# pj7.net
KiCad netlist of a schematic drawn in EAGLE
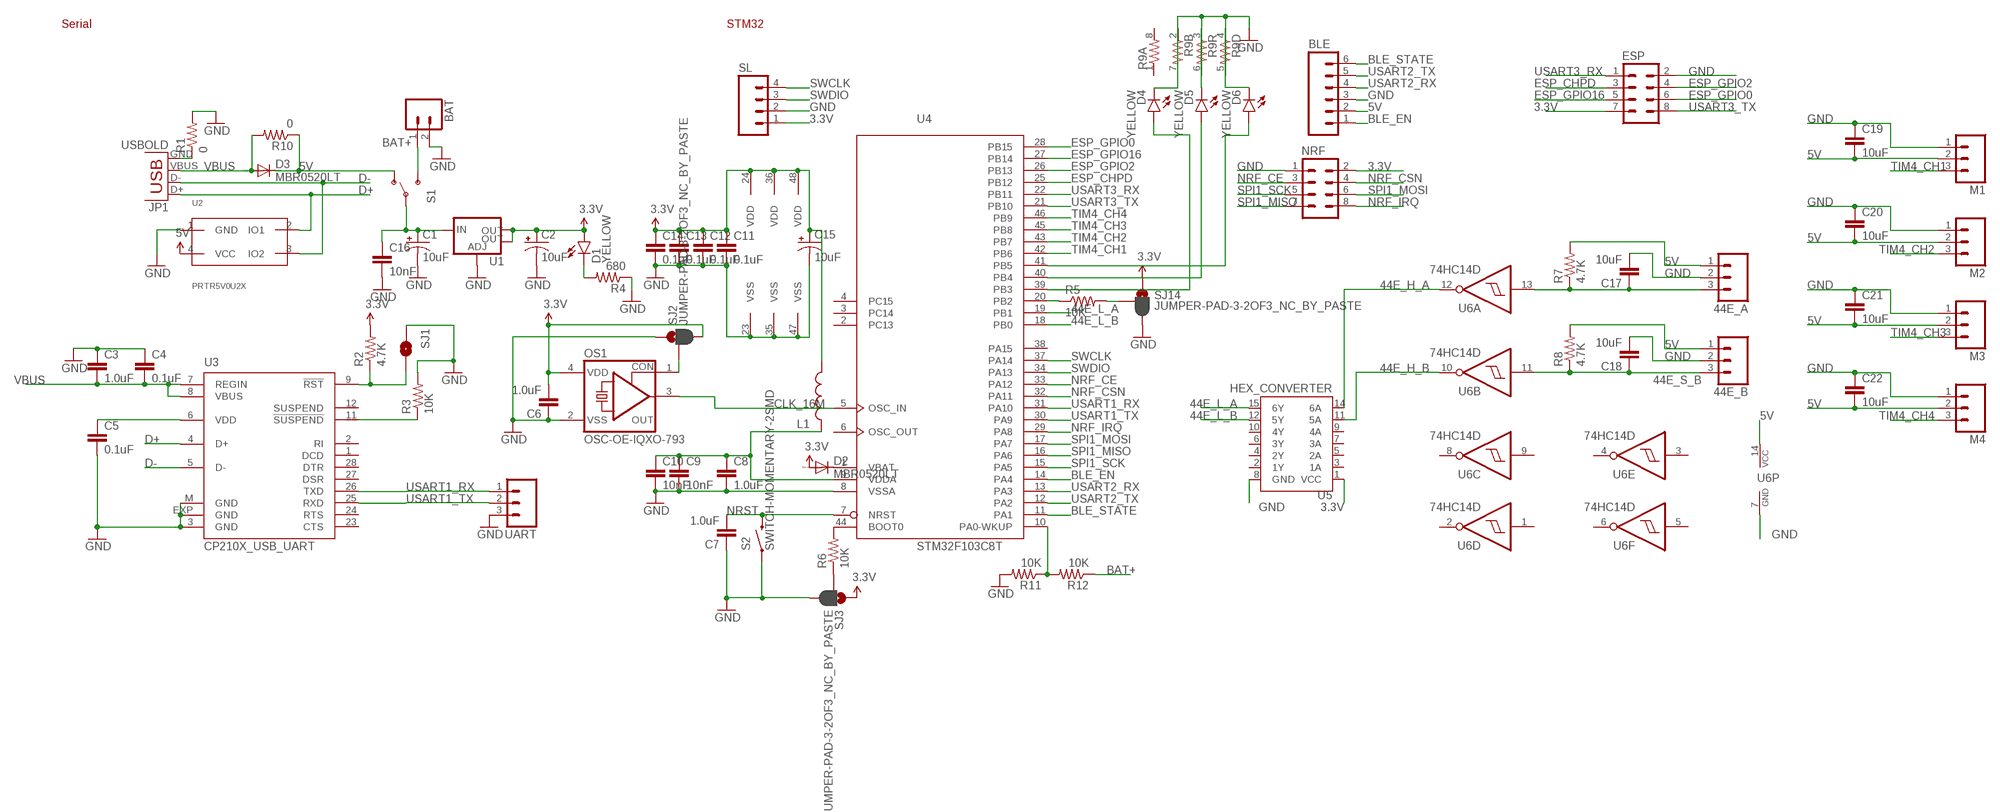
[diagram p0: schematic, sheet 1]

(export (version "E")
  (design (tool "Eeschema 10.0.6"))
  (components
    (comp (ref "44E_A")
      (value "M03LOCK")
      (footprint "eagle-import:1X03_LOCK")
      (libsource (lib "eagle-import") (part "M03LOCK"))
    )
    (comp (ref "44E_B")
      (value "M03LOCK")
      (footprint "eagle-import:1X03_LOCK")
      (libsource (lib "eagle-import") (part "M03LOCK"))
    )
    (comp (ref "BAT")
      (value "M02LOCK")
      (footprint "eagle-import:1X02_LOCK")
      (libsource (lib "eagle-import") (part "M02LOCK"))
    )
    (comp (ref "BLE")
      (value "M06LOCK")
      (footprint "eagle-import:1X06_LOCK")
      (libsource (lib "eagle-import") (part "M06LOCK"))
    )
    (comp (ref "C1")
      (value "10uF")
      (footprint "eagle-import:EIA3216")
      (libsource (lib "eagle-import") (part "10UF-16V-10%(TANT)"))
    )
    (comp (ref "C2")
      (value "10uF")
      (footprint "eagle-import:EIA3216")
      (libsource (lib "eagle-import") (part "10UF-16V-10%(TANT)"))
    )
    (comp (ref "C3")
      (value "1.0uF")
      (footprint "eagle-import:0603-CAP")
      (libsource (lib "eagle-import") (part "1.0UF-16V-10%(0603)"))
    )
    (comp (ref "C4")
      (value "0.1uF")
      (footprint "eagle-import:0603-CAP")
      (libsource (lib "eagle-import") (part "0.1UF-25V-5%(0603)"))
    )
    (comp (ref "C5")
      (value "0.1uF")
      (footprint "eagle-import:0603-CAP")
      (libsource (lib "eagle-import") (part "0.1UF-25V-5%(0603)"))
    )
    (comp (ref "C6")
      (value "1.0uF")
      (footprint "eagle-import:0603-CAP")
      (libsource (lib "eagle-import") (part "1.0UF-16V-10%(0603)"))
    )
    (comp (ref "C7")
      (value "1.0uF")
      (footprint "eagle-import:0603-CAP")
      (libsource (lib "eagle-import") (part "1.0UF-16V-10%(0603)"))
    )
    (comp (ref "C8")
      (value "1.0uF")
      (footprint "eagle-import:0603-CAP")
      (libsource (lib "eagle-import") (part "1.0UF-16V-10%(0603)"))
    )
    (comp (ref "C9")
      (value "10nF")
      (footprint "eagle-import:0603-CAP")
      (libsource (lib "eagle-import") (part "10NF/10000PF-50V-10%(0603)"))
    )
    (comp (ref "C10")
      (value "10nF")
      (footprint "eagle-import:0603-CAP")
      (libsource (lib "eagle-import") (part "10NF/10000PF-50V-10%(0603)"))
    )
    (comp (ref "C11")
      (value "0.1uF")
      (footprint "eagle-import:0603-CAP")
      (libsource (lib "eagle-import") (part "0.1UF-25V-5%(0603)"))
    )
    (comp (ref "C12")
      (value "0.1uF")
      (footprint "eagle-import:0603-CAP")
      (libsource (lib "eagle-import") (part "0.1UF-25V-5%(0603)"))
    )
    (comp (ref "C13")
      (value "0.1uF")
      (footprint "eagle-import:0603-CAP")
      (libsource (lib "eagle-import") (part "0.1UF-25V-5%(0603)"))
    )
    (comp (ref "C14")
      (value "0.1uF")
      (footprint "eagle-import:0603-CAP")
      (libsource (lib "eagle-import") (part "0.1UF-25V-5%(0603)"))
    )
    (comp (ref "C15")
      (value "10uF")
      (footprint "eagle-import:EIA3216")
      (libsource (lib "eagle-import") (part "10UF-16V-10%(TANT)"))
    )
    (comp (ref "C16")
      (value "10nF")
      (footprint "eagle-import:0603-CAP")
      (libsource (lib "eagle-import") (part "10NF/10000PF-50V-10%(0603)"))
    )
    (comp (ref "C17")
      (value "10uF")
      (footprint "eagle-import:0603-CAP")
      (libsource (lib "eagle-import") (part "10UF-6.3V-20%(0603)"))
    )
    (comp (ref "C18")
      (value "10uF")
      (footprint "eagle-import:0603-CAP")
      (libsource (lib "eagle-import") (part "10UF-6.3V-20%(0603)"))
    )
    (comp (ref "C19")
      (value "10uF")
      (footprint "eagle-import:0603-CAP")
      (libsource (lib "eagle-import") (part "10UF-6.3V-20%(0603)"))
    )
    (comp (ref "C20")
      (value "10uF")
      (footprint "eagle-import:0603-CAP")
      (libsource (lib "eagle-import") (part "10UF-6.3V-20%(0603)"))
    )
    (comp (ref "C21")
      (value "10uF")
      (footprint "eagle-import:0603-CAP")
      (libsource (lib "eagle-import") (part "10UF-6.3V-20%(0603)"))
    )
    (comp (ref "C22")
      (value "10uF")
      (footprint "eagle-import:0603-CAP")
      (libsource (lib "eagle-import") (part "10UF-6.3V-20%(0603)"))
    )
    (comp (ref "D1")
      (value "YELLOW")
      (footprint "eagle-import:LED-1206")
      (libsource (lib "eagle-import") (part "LED-YELLOW1206"))
    )
    (comp (ref "D2")
      (value "MBR0520LT")
      (footprint "eagle-import:SOD123")
      (libsource (lib "eagle-import") (part "MBR0520LT"))
    )
    (comp (ref "D3")
      (value "MBR0520LT")
      (footprint "eagle-import:SOD123")
      (libsource (lib "eagle-import") (part "MBR0520LT"))
    )
    (comp (ref "D4")
      (value "YELLOW")
      (footprint "eagle-import:LED-1206")
      (libsource (lib "eagle-import") (part "LED-YELLOW1206"))
    )
    (comp (ref "D5")
      (value "YELLOW")
      (footprint "eagle-import:LED-1206")
      (libsource (lib "eagle-import") (part "LED-YELLOW1206"))
    )
    (comp (ref "D6")
      (value "YELLOW")
      (footprint "eagle-import:LED-1206")
      (libsource (lib "eagle-import") (part "LED-YELLOW1206"))
    )
    (comp (ref "ESP")
      (value "M04X2DIP")
      (footprint "eagle-import:2X4")
      (libsource (lib "eagle-import") (part "M04X2DIP"))
    )
    (comp (ref "JP1")
      (value "USBOLD")
      (footprint "eagle-import:USB-MINIB-OLD")
      (libsource (lib "eagle-import") (part "USBOLD"))
    )
    (comp (ref "L1")
      (value "INDUCTOR0603")
      (footprint "eagle-import:0603")
      (libsource (lib "eagle-import") (part "INDUCTOR0603"))
    )
    (comp (ref "M1")
      (value "M03LOCK")
      (footprint "eagle-import:1X03_LOCK")
      (libsource (lib "eagle-import") (part "M03LOCK"))
    )
    (comp (ref "M2")
      (value "M03LOCK")
      (footprint "eagle-import:1X03_LOCK")
      (libsource (lib "eagle-import") (part "M03LOCK"))
    )
    (comp (ref "M3")
      (value "M03LOCK")
      (footprint "eagle-import:1X03_LOCK")
      (libsource (lib "eagle-import") (part "M03LOCK"))
    )
    (comp (ref "M4")
      (value "M03LOCK")
      (footprint "eagle-import:1X03_LOCK")
      (libsource (lib "eagle-import") (part "M03LOCK"))
    )
    (comp (ref "NRF")
      (value "M04X2DIP")
      (footprint "eagle-import:2X4")
      (libsource (lib "eagle-import") (part "M04X2DIP"))
    )
    (comp (ref "OS1")
      (value "OSC-OE-IQXO-793")
      (footprint "eagle-import:2.5X2-4-PAD")
      (libsource (lib "eagle-import") (part "OSC-OE-IQXO-793"))
    )
    (comp (ref "R1")
      (value "0")
      (footprint "eagle-import:0603")
      (libsource (lib "eagle-import") (part "0OHM-1/10W-5%(0603)"))
    )
    (comp (ref "R2")
      (value "4.7K")
      (footprint "eagle-import:0603-RES")
      (libsource (lib "eagle-import") (part "4.7KOHM-1/10W-1%(0603)"))
    )
    (comp (ref "R3")
      (value "10K")
      (footprint "eagle-import:0603-RES")
      (libsource (lib "eagle-import") (part "4.7KOHM-1/10W-1%(0603)"))
    )
    (comp (ref "R4")
      (value "680")
      (footprint "eagle-import:0603-RES")
      (libsource (lib "eagle-import") (part "680OHM1/10W5%(0603)"))
    )
    (comp (ref "R5")
      (value "10K")
      (footprint "eagle-import:0603-RES")
      (libsource (lib "eagle-import") (part "10KOHM-1/10W-1%(0603)0603"))
    )
    (comp (ref "R6")
      (value "10K")
      (footprint "eagle-import:0603-RES")
      (libsource (lib "eagle-import") (part "10KOHM-1/10W-1%(0603)0603"))
    )
    (comp (ref "R7")
      (value "4.7K")
      (footprint "eagle-import:0603-RES")
      (libsource (lib "eagle-import") (part "4.7KOHM-1/10W-1%(0603)"))
    )
    (comp (ref "R8")
      (value "4.7K")
      (footprint "eagle-import:0603-RES")
      (libsource (lib "eagle-import") (part "4.7KOHM-1/10W-1%(0603)"))
    )
    (comp (ref "R9")
      (value "RESISTOR-ARRAY0603-ARV")
      (footprint "eagle-import:0603-ARV")
      (libsource (lib "eagle-import") (part "RESISTOR-ARRAY0603-ARV"))
    )
    (comp (ref "R10")
      (value "0")
      (footprint "eagle-import:0603")
      (libsource (lib "eagle-import") (part "0OHM-1/10W-5%(0603)"))
    )
    (comp (ref "R11")
      (value "10K")
      (footprint "eagle-import:0603-RES")
      (libsource (lib "eagle-import") (part "10KOHM-1/10W-1%(0603)0603"))
    )
    (comp (ref "R12")
      (value "10K")
      (footprint "eagle-import:0603-RES")
      (libsource (lib "eagle-import") (part "10KOHM-1/10W-1%(0603)0603"))
    )
    (comp (ref "S1")
      (value "SWITCH-SPDTSMD")
      (footprint "eagle-import:AYZ0202")
      (libsource (lib "eagle-import") (part "SWITCH-SPDTSMD"))
    )
    (comp (ref "S2")
      (value "SWITCH-MOMENTARY-2SMD")
      (footprint "eagle-import:TACTILE-SWITCH-SMD")
      (libsource (lib "eagle-import") (part "SWITCH-MOMENTARY-2SMD"))
    )
    (comp (ref "SJ1")
      (value "JUMPER-PAD-2-NOYES_SILK")
      (footprint "eagle-import:PAD-JUMPER-2-NO_YES_SILK")
      (libsource (lib "eagle-import") (part "JUMPER-PAD-2-NOYES_SILK"))
    )
    (comp (ref "SJ2")
      (value "JUMPER-PAD-3-2OF3_NC_BY_PASTE")
      (footprint "eagle-import:PAD-JUMPER-3-2OF3_NC_BY_PASTE_YES_SILK_FULL_BOX")
      (libsource (lib "eagle-import") (part "JUMPER-PAD-3-2OF3_NC_BY_PASTE"))
    )
    (comp (ref "SJ3")
      (value "JUMPER-PAD-3-2OF3_NC_BY_PASTE")
      (footprint "eagle-import:PAD-JUMPER-3-2OF3_NC_BY_PASTE_YES_SILK_FULL_BOX")
      (libsource (lib "eagle-import") (part "JUMPER-PAD-3-2OF3_NC_BY_PASTE"))
    )
    (comp (ref "SJ14")
      (value "JUMPER-PAD-3-2OF3_NC_BY_PASTE")
      (footprint "eagle-import:PAD-JUMPER-3-2OF3_NC_BY_PASTE_YES_SILK_FULL_BOX")
      (libsource (lib "eagle-import") (part "JUMPER-PAD-3-2OF3_NC_BY_PASTE"))
    )
    (comp (ref "SL")
      (value "M04LOCK")
      (footprint "eagle-import:1X04_LOCK")
      (libsource (lib "eagle-import") (part "M04LOCK"))
    )
    (comp (ref "U1")
      (value "V_REG_LM1117SOT223")
      (footprint "eagle-import:SOT223")
      (libsource (lib "eagle-import") (part "V_REG_LM1117SOT223"))
    )
    (comp (ref "U2")
      (value "PRTR5V0U2X")
      (footprint "eagle-import:SOT143")
      (libsource (lib "eagle-import") (part "PRTR5V0U2X"))
    )
    (comp (ref "U3")
      (value "CP210X_USB_UART")
      (footprint "eagle-import:MLP28")
      (libsource (lib "eagle-import") (part "CP210X_USB_UART"))
    )
    (comp (ref "U4")
      (value "STM32F103C8T")
      (footprint "eagle-import:LQFP48")
      (libsource (lib "eagle-import") (part "STM32F103CT8"))
    )
    (comp (ref "U5")
      (value "HEX_CONVERTER")
      (footprint "eagle-import:SO016")
      (libsource (lib "eagle-import") (part "HEX_CONVERTER"))
    )
    (comp (ref "U6")
      (value "74HC14D")
      (footprint "eagle-import:SO14")
      (libsource (lib "eagle-import") (part "7414DHC"))
    )
    (comp (ref "UART")
      (value "M03LOCK")
      (footprint "eagle-import:1X03_LOCK")
      (libsource (lib "eagle-import") (part "M03LOCK"))
    )
  )
  (nets
    (net (code "1") (name "/44E_H_A") (class "Default")
      (node (ref "U5") (pin "14") (pinfunction "6A_14") (pintype "bidirectional"))
      (node (ref "U6") (pin "12") (pinfunction "O_12") (pintype "output"))
    )
    (net (code "2") (name "/44E_H_B") (class "Default")
      (node (ref "U5") (pin "11") (pinfunction "5A_11") (pintype "bidirectional"))
      (node (ref "U6") (pin "10") (pinfunction "O_10") (pintype "output"))
    )
    (net (code "3") (name "/44E_L_A") (class "Default")
      (node (ref "U4") (pin "19") (pinfunction "PB1_19") (pintype "bidirectional"))
      (node (ref "U5") (pin "15") (pinfunction "6Y_15") (pintype "bidirectional"))
    )
    (net (code "4") (name "/44E_L_B") (class "Default")
      (node (ref "U4") (pin "18") (pinfunction "PB0_18") (pintype "bidirectional"))
      (node (ref "U5") (pin "12") (pinfunction "5Y_12") (pintype "bidirectional"))
    )
    (net (code "5") (name "/44E_S_B") (class "Default")
      (node (ref "44E_B") (pin "3") (pinfunction "3_3") (pintype "passive"))
      (node (ref "C18") (pin "1") (pinfunction "1_1") (pintype "passive"))
      (node (ref "R8") (pin "1") (pinfunction "1_1") (pintype "passive"))
      (node (ref "U6") (pin "11") (pinfunction "I_11") (pintype "input"))
    )
    (net (code "6") (name "/BAT+") (class "Default")
      (node (ref "BAT") (pin "1") (pinfunction "1_1") (pintype "passive"))
      (node (ref "R12") (pin "1") (pinfunction "1_1") (pintype "passive"))
      (node (ref "S1") (pin "3") (pinfunction "S_3") (pintype "passive"))
    )
    (net (code "7") (name "/BLE_EN") (class "Default")
      (node (ref "BLE") (pin "1") (pinfunction "1_1") (pintype "passive"))
      (node (ref "U4") (pin "14") (pinfunction "PA4_14") (pintype "bidirectional"))
    )
    (net (code "8") (name "/BLE_STATE") (class "Default")
      (node (ref "BLE") (pin "6") (pinfunction "6_6") (pintype "passive"))
      (node (ref "U4") (pin "11") (pinfunction "PA1_11") (pintype "bidirectional"))
    )
    (net (code "9") (name "/CLK_16M") (class "Default")
      (node (ref "OS1") (pin "3") (pinfunction "OUT_3") (pintype "output"))
      (node (ref "U4") (pin "5") (pinfunction "OSC_IN_5") (pintype "bidirectional"))
    )
    (net (code "10") (name "/D+") (class "Default")
      (node (ref "JP1") (pin "D+") (pinfunction "D+_D+") (pintype "bidirectional"))
      (node (ref "U2") (pin "2") (pinfunction "IO1_2") (pintype "bidirectional"))
      (node (ref "U3") (pin "4") (pinfunction "D+_4") (pintype "bidirectional"))
    )
    (net (code "11") (name "/D-") (class "Default")
      (node (ref "JP1") (pin "D-") (pinfunction "D-_D-") (pintype "bidirectional"))
      (node (ref "U2") (pin "3") (pinfunction "IO2_3") (pintype "bidirectional"))
      (node (ref "U3") (pin "5") (pinfunction "D-_5") (pintype "bidirectional"))
    )
    (net (code "12") (name "/ESP_CHPD") (class "Default")
      (node (ref "ESP") (pin "3") (pinfunction "3_3") (pintype "passive"))
      (node (ref "U4") (pin "25") (pinfunction "PB12_25") (pintype "bidirectional"))
    )
    (net (code "13") (name "/ESP_GPIO0") (class "Default")
      (node (ref "ESP") (pin "6") (pinfunction "6_6") (pintype "passive"))
      (node (ref "U4") (pin "28") (pinfunction "PB15_28") (pintype "bidirectional"))
    )
    (net (code "14") (name "/ESP_GPIO2") (class "Default")
      (node (ref "ESP") (pin "4") (pinfunction "4_4") (pintype "passive"))
      (node (ref "U4") (pin "26") (pinfunction "PB13_26") (pintype "bidirectional"))
    )
    (net (code "15") (name "/ESP_GPIO16") (class "Default")
      (node (ref "ESP") (pin "5") (pinfunction "5_5") (pintype "passive"))
      (node (ref "U4") (pin "27") (pinfunction "PB14_27") (pintype "bidirectional"))
    )
    (net (code "16") (name "/NRF_CE") (class "Default")
      (node (ref "NRF") (pin "3") (pinfunction "3_3") (pintype "passive"))
      (node (ref "U4") (pin "33") (pinfunction "PA12_33") (pintype "bidirectional"))
    )
    (net (code "17") (name "/NRF_CSN") (class "Default")
      (node (ref "NRF") (pin "4") (pinfunction "4_4") (pintype "passive"))
      (node (ref "U4") (pin "32") (pinfunction "PA11_32") (pintype "bidirectional"))
    )
    (net (code "18") (name "/NRF_IRQ") (class "Default")
      (node (ref "NRF") (pin "8") (pinfunction "8_8") (pintype "passive"))
      (node (ref "U4") (pin "29") (pinfunction "PA8_29") (pintype "bidirectional"))
    )
    (net (code "19") (name "/NRST") (class "Default")
      (node (ref "C7") (pin "2") (pinfunction "2_2") (pintype "passive"))
      (node (ref "S2") (pin "3") (pinfunction "2_3") (pintype "passive"))
      (node (ref "U4") (pin "7") (pinfunction "NRST_7") (pintype "bidirectional"))
    )
    (net (code "20") (name "/SPI1_MISO") (class "Default")
      (node (ref "NRF") (pin "7") (pinfunction "7_7") (pintype "passive"))
      (node (ref "U4") (pin "16") (pinfunction "PA6_16") (pintype "bidirectional"))
    )
    (net (code "21") (name "/SPI1_MOSI") (class "Default")
      (node (ref "NRF") (pin "6") (pinfunction "6_6") (pintype "passive"))
      (node (ref "U4") (pin "17") (pinfunction "PA7_17") (pintype "bidirectional"))
    )
    (net (code "22") (name "/SPI1_SCK") (class "Default")
      (node (ref "NRF") (pin "5") (pinfunction "5_5") (pintype "passive"))
      (node (ref "U4") (pin "15") (pinfunction "PA5_15") (pintype "bidirectional"))
    )
    (net (code "23") (name "/SWCLK") (class "Default")
      (node (ref "SL") (pin "4") (pinfunction "4_4") (pintype "passive"))
      (node (ref "U4") (pin "37") (pinfunction "PA14_37") (pintype "bidirectional"))
    )
    (net (code "24") (name "/SWDIO") (class "Default")
      (node (ref "SL") (pin "3") (pinfunction "3_3") (pintype "passive"))
      (node (ref "U4") (pin "34") (pinfunction "PA13_34") (pintype "bidirectional"))
    )
    (net (code "25") (name "/TIM4_CH1") (class "Default")
      (node (ref "M1") (pin "3") (pinfunction "3_3") (pintype "passive"))
      (node (ref "U4") (pin "42") (pinfunction "PB6_42") (pintype "bidirectional"))
    )
    (net (code "26") (name "/TIM4_CH2") (class "Default")
      (node (ref "M2") (pin "3") (pinfunction "3_3") (pintype "passive"))
      (node (ref "U4") (pin "43") (pinfunction "PB7_43") (pintype "bidirectional"))
    )
    (net (code "27") (name "/TIM4_CH3") (class "Default")
      (node (ref "M3") (pin "3") (pinfunction "3_3") (pintype "passive"))
      (node (ref "U4") (pin "45") (pinfunction "PB8_45") (pintype "bidirectional"))
    )
    (net (code "28") (name "/TIM4_CH4") (class "Default")
      (node (ref "M4") (pin "3") (pinfunction "3_3") (pintype "passive"))
      (node (ref "U4") (pin "46") (pinfunction "PB9_46") (pintype "bidirectional"))
    )
    (net (code "29") (name "/USART1_RX") (class "Default")
      (node (ref "U3") (pin "26") (pinfunction "TXD_26") (pintype "output"))
      (node (ref "U4") (pin "31") (pinfunction "PA10_31") (pintype "bidirectional"))
      (node (ref "UART") (pin "1") (pinfunction "1_1") (pintype "passive"))
    )
    (net (code "30") (name "/USART1_TX") (class "Default")
      (node (ref "U3") (pin "25") (pinfunction "RXD_25") (pintype "input"))
      (node (ref "U4") (pin "30") (pinfunction "PA9_30") (pintype "bidirectional"))
      (node (ref "UART") (pin "2") (pinfunction "2_2") (pintype "passive"))
    )
    (net (code "31") (name "/USART2_RX") (class "Default")
      (node (ref "BLE") (pin "4") (pinfunction "4_4") (pintype "passive"))
      (node (ref "U4") (pin "13") (pinfunction "PA3_13") (pintype "bidirectional"))
    )
    (net (code "32") (name "/USART2_TX") (class "Default")
      (node (ref "BLE") (pin "5") (pinfunction "5_5") (pintype "passive"))
      (node (ref "U4") (pin "12") (pinfunction "PA2_12") (pintype "bidirectional"))
    )
    (net (code "33") (name "/USART3_RX") (class "Default")
      (node (ref "ESP") (pin "1") (pinfunction "1_1") (pintype "passive"))
      (node (ref "U4") (pin "22") (pinfunction "PB11_22") (pintype "bidirectional"))
    )
    (net (code "34") (name "/USART3_TX") (class "Default")
      (node (ref "ESP") (pin "8") (pinfunction "8_8") (pintype "passive"))
      (node (ref "U4") (pin "21") (pinfunction "PB10_21") (pintype "bidirectional"))
    )
    (net (code "35") (name "/VBUS") (class "Default")
      (node (ref "C3") (pin "2") (pinfunction "2_2") (pintype "passive"))
      (node (ref "C4") (pin "2") (pinfunction "2_2") (pintype "passive"))
      (node (ref "D3") (pin "A") (pinfunction "A_A") (pintype "passive"))
      (node (ref "JP1") (pin "VBUS") (pinfunction "VBUS_VBUS") (pintype "bidirectional"))
      (node (ref "R10") (pin "2") (pinfunction "2_2") (pintype "passive"))
      (node (ref "U3") (pin "7") (pinfunction "REGIN_7") (pintype "passive"))
      (node (ref "U3") (pin "8") (pinfunction "VBUS_8") (pintype "input"))
    )
    (net (code "36") (name "3.3V") (class "Default")
      (node (ref "C11") (pin "1") (pinfunction "1_1") (pintype "passive"))
      (node (ref "C12") (pin "1") (pinfunction "1_1") (pintype "passive"))
      (node (ref "C13") (pin "1") (pinfunction "1_1") (pintype "passive"))
      (node (ref "C14") (pin "1") (pinfunction "1_1") (pintype "passive"))
      (node (ref "C15") (pin "A") (pinfunction "+_A") (pintype "passive"))
      (node (ref "C2") (pin "A") (pinfunction "+_A") (pintype "passive"))
      (node (ref "C6") (pin "2") (pinfunction "2_2") (pintype "passive"))
      (node (ref "D1") (pin "A") (pinfunction "A_A") (pintype "passive"))
      (node (ref "D2") (pin "A") (pinfunction "A_A") (pintype "passive"))
      (node (ref "ESP") (pin "7") (pinfunction "7_7") (pintype "passive"))
      (node (ref "L1") (pin "2") (pinfunction "2_2") (pintype "passive"))
      (node (ref "NRF") (pin "2") (pinfunction "2_2") (pintype "passive"))
      (node (ref "OS1") (pin "4") (pinfunction "VDD_4") (pintype "power_in"))
      (node (ref "R2") (pin "2") (pinfunction "2_2") (pintype "passive"))
      (node (ref "SJ14") (pin "1") (pinfunction "1_1") (pintype "passive"))
      (node (ref "SJ2") (pin "3") (pinfunction "3_3") (pintype "passive"))
      (node (ref "SJ3") (pin "1") (pinfunction "1_1") (pintype "passive"))
      (node (ref "SL") (pin "1") (pinfunction "1_1") (pintype "passive"))
      (node (ref "U1") (pin "2") (pinfunction "OUT_2") (pintype "output"))
      (node (ref "U1") (pin "4") (pinfunction "OUT_4") (pintype "output"))
      (node (ref "U4") (pin "24") (pinfunction "VDD_24") (pintype "power_in"))
      (node (ref "U4") (pin "36") (pinfunction "VDD_36") (pintype "power_in"))
      (node (ref "U4") (pin "48") (pinfunction "VDD_48") (pintype "power_in"))
      (node (ref "U5") (pin "1") (pinfunction "VCC_1") (pintype "bidirectional"))
    )
    (net (code "37") (name "5V") (class "Default")
      (node (ref "44E_A") (pin "1") (pinfunction "1_1") (pintype "passive"))
      (node (ref "44E_B") (pin "1") (pinfunction "1_1") (pintype "passive"))
      (node (ref "BLE") (pin "2") (pinfunction "2_2") (pintype "passive"))
      (node (ref "C19") (pin "2") (pinfunction "2_2") (pintype "passive"))
      (node (ref "C20") (pin "2") (pinfunction "2_2") (pintype "passive"))
      (node (ref "C21") (pin "2") (pinfunction "2_2") (pintype "passive"))
      (node (ref "C22") (pin "2") (pinfunction "2_2") (pintype "passive"))
      (node (ref "D3") (pin "C") (pinfunction "C_C") (pintype "passive"))
      (node (ref "M1") (pin "2") (pinfunction "2_2") (pintype "passive"))
      (node (ref "M2") (pin "2") (pinfunction "2_2") (pintype "passive"))
      (node (ref "M3") (pin "2") (pinfunction "2_2") (pintype "passive"))
      (node (ref "M4") (pin "2") (pinfunction "2_2") (pintype "passive"))
      (node (ref "R10") (pin "1") (pinfunction "1_1") (pintype "passive"))
      (node (ref "R7") (pin "2") (pinfunction "2_2") (pintype "passive"))
      (node (ref "R8") (pin "2") (pinfunction "2_2") (pintype "passive"))
      (node (ref "S1") (pin "1") (pinfunction "O_1") (pintype "passive"))
      (node (ref "U2") (pin "4") (pinfunction "VCC_4") (pintype "bidirectional"))
      (node (ref "U6") (pin "14") (pinfunction "VCC_14") (pintype "power_in"))
    )
    (net (code "38") (name "GND") (class "Default")
      (node (ref "44E_A") (pin "2") (pinfunction "2_2") (pintype "passive"))
      (node (ref "44E_B") (pin "2") (pinfunction "2_2") (pintype "passive"))
      (node (ref "BAT") (pin "2") (pinfunction "2_2") (pintype "passive"))
      (node (ref "BLE") (pin "3") (pinfunction "3_3") (pintype "passive"))
      (node (ref "C1") (pin "C") (pinfunction "-_C") (pintype "passive"))
      (node (ref "C10") (pin "2") (pinfunction "2_2") (pintype "passive"))
      (node (ref "C11") (pin "2") (pinfunction "2_2") (pintype "passive"))
      (node (ref "C12") (pin "2") (pinfunction "2_2") (pintype "passive"))
      (node (ref "C13") (pin "2") (pinfunction "2_2") (pintype "passive"))
      (node (ref "C14") (pin "2") (pinfunction "2_2") (pintype "passive"))
      (node (ref "C15") (pin "C") (pinfunction "-_C") (pintype "passive"))
      (node (ref "C16") (pin "2") (pinfunction "2_2") (pintype "passive"))
      (node (ref "C17") (pin "2") (pinfunction "2_2") (pintype "passive"))
      (node (ref "C18") (pin "2") (pinfunction "2_2") (pintype "passive"))
      (node (ref "C19") (pin "1") (pinfunction "1_1") (pintype "passive"))
      (node (ref "C2") (pin "C") (pinfunction "-_C") (pintype "passive"))
      (node (ref "C20") (pin "1") (pinfunction "1_1") (pintype "passive"))
      (node (ref "C21") (pin "1") (pinfunction "1_1") (pintype "passive"))
      (node (ref "C22") (pin "1") (pinfunction "1_1") (pintype "passive"))
      (node (ref "C3") (pin "1") (pinfunction "1_1") (pintype "passive"))
      (node (ref "C4") (pin "1") (pinfunction "1_1") (pintype "passive"))
      (node (ref "C5") (pin "2") (pinfunction "2_2") (pintype "passive"))
      (node (ref "C6") (pin "1") (pinfunction "1_1") (pintype "passive"))
      (node (ref "C7") (pin "1") (pinfunction "1_1") (pintype "passive"))
      (node (ref "C8") (pin "2") (pinfunction "2_2") (pintype "passive"))
      (node (ref "C9") (pin "2") (pinfunction "2_2") (pintype "passive"))
      (node (ref "ESP") (pin "2") (pinfunction "2_2") (pintype "passive"))
      (node (ref "M1") (pin "1") (pinfunction "1_1") (pintype "passive"))
      (node (ref "M2") (pin "1") (pinfunction "1_1") (pintype "passive"))
      (node (ref "M3") (pin "1") (pinfunction "1_1") (pintype "passive"))
      (node (ref "M4") (pin "1") (pinfunction "1_1") (pintype "passive"))
      (node (ref "NRF") (pin "1") (pinfunction "1_1") (pintype "passive"))
      (node (ref "OS1") (pin "2") (pinfunction "VSS_2") (pintype "power_in"))
      (node (ref "R1") (pin "2") (pinfunction "2_2") (pintype "passive"))
      (node (ref "R11") (pin "2") (pinfunction "2_2") (pintype "passive"))
      (node (ref "R3") (pin "2") (pinfunction "2_2") (pintype "passive"))
      (node (ref "R4") (pin "1") (pinfunction "1_1") (pintype "passive"))
      (node (ref "R9") (pin "5") (pinfunction "2_5") (pintype "passive"))
      (node (ref "R9") (pin "6") (pinfunction "2_6") (pintype "passive"))
      (node (ref "R9") (pin "7") (pinfunction "2_7") (pintype "passive"))
      (node (ref "S2") (pin "1") (pinfunction "1_1") (pintype "passive"))
      (node (ref "SJ1") (pin "2") (pinfunction "2_2") (pintype "passive"))
      (node (ref "SJ14") (pin "3") (pinfunction "3_3") (pintype "passive"))
      (node (ref "SJ2") (pin "1") (pinfunction "1_1") (pintype "passive"))
      (node (ref "SJ3") (pin "3") (pinfunction "3_3") (pintype "passive"))
      (node (ref "SL") (pin "2") (pinfunction "2_2") (pintype "passive"))
      (node (ref "U1") (pin "1") (pinfunction "ADJ_1") (pintype "input"))
      (node (ref "U2") (pin "1") (pinfunction "GND_1") (pintype "bidirectional"))
      (node (ref "U3") (pin "3") (pinfunction "GND_3") (pintype "power_in"))
      (node (ref "U3") (pin "EXP") (pinfunction "GND_EXP") (pintype "power_in"))
      (node (ref "U3") (pin "M") (pinfunction "GND_M") (pintype "power_in"))
      (node (ref "U4") (pin "23") (pinfunction "VSS_23") (pintype "power_in"))
      (node (ref "U4") (pin "35") (pinfunction "VSS_35") (pintype "power_in"))
      (node (ref "U4") (pin "47") (pinfunction "VSS_47") (pintype "power_in"))
      (node (ref "U4") (pin "8") (pinfunction "VSSA_8") (pintype "power_in"))
      (node (ref "U5") (pin "8") (pinfunction "GND_8") (pintype "bidirectional"))
      (node (ref "U6") (pin "7") (pinfunction "GND_7") (pintype "power_in"))
      (node (ref "UART") (pin "3") (pinfunction "3_3") (pintype "passive"))
    )
    (net (code "39") (name "Net-(C1-+)") (class "Default")
      (node (ref "C1") (pin "A") (pinfunction "+_A") (pintype "passive"))
      (node (ref "C16") (pin "1") (pinfunction "1_1") (pintype "passive"))
      (node (ref "S1") (pin "2") (pinfunction "P_2") (pintype "passive"))
      (node (ref "U1") (pin "3") (pinfunction "IN_3") (pintype "input"))
    )
    (net (code "40") (name "Net-(D1-PadC)") (class "Default")
      (node (ref "D1") (pin "C") (pinfunction "C_C") (pintype "passive"))
      (node (ref "R4") (pin "2") (pinfunction "2_2") (pintype "passive"))
    )
    (net (code "41") (name "Net-(JP1-PadGND)") (class "Default")
      (node (ref "JP1") (pin "GND") (pinfunction "GND_GND") (pintype "bidirectional"))
      (node (ref "R1") (pin "1") (pinfunction "1_1") (pintype "passive"))
    )
    (net (code "42") (name "Net-(OS1-CON)") (class "Default")
      (node (ref "OS1") (pin "1") (pinfunction "CON_1") (pintype "input"))
      (node (ref "SJ2") (pin "2") (pinfunction "2_2") (pintype "passive"))
    )
    (net (code "43") (name "Net-(R5-Pad2)") (class "Default")
      (node (ref "R5") (pin "2") (pinfunction "2_2") (pintype "passive"))
      (node (ref "SJ14") (pin "2") (pinfunction "2_2") (pintype "passive"))
    )
    (net (code "44") (name "Net-(R6-Pad1)") (class "Default")
      (node (ref "R6") (pin "1") (pinfunction "1_1") (pintype "passive"))
      (node (ref "SJ3") (pin "2") (pinfunction "2_2") (pintype "passive"))
    )
    (net (code "45") (name "Net-(R9B-1)") (class "Default")
      (node (ref "D4") (pin "C") (pinfunction "C_C") (pintype "passive"))
      (node (ref "R9") (pin "2") (pinfunction "1_2") (pintype "passive"))
    )
    (net (code "46") (name "Net-(R9C-1)") (class "Default")
      (node (ref "D6") (pin "C") (pinfunction "C_C") (pintype "passive"))
      (node (ref "R9") (pin "4") (pinfunction "1_4") (pintype "passive"))
    )
    (net (code "47") (name "Net-(R9D-1)") (class "Default")
      (node (ref "D5") (pin "C") (pinfunction "C_C") (pintype "passive"))
      (node (ref "R9") (pin "3") (pinfunction "1_3") (pintype "passive"))
    )
    (net (code "48") (name "Net-(U3-VDD)") (class "Default")
      (node (ref "C5") (pin "1") (pinfunction "1_1") (pintype "passive"))
      (node (ref "U3") (pin "6") (pinfunction "VDD_6") (pintype "power_in"))
    )
    (net (code "49") (name "Net-(U3-~{RST})") (class "Default")
      (node (ref "R2") (pin "1") (pinfunction "1_1") (pintype "passive"))
      (node (ref "SJ1") (pin "1") (pinfunction "1_1") (pintype "passive"))
      (node (ref "U3") (pin "9") (pinfunction "~{RST}_9") (pintype "bidirectional"))
    )
    (net (code "50") (name "Net-(U3-~{SUSPEND})") (class "Default")
      (node (ref "R3") (pin "1") (pinfunction "1_1") (pintype "passive"))
      (node (ref "U3") (pin "11") (pinfunction "~{SUSPEND}_11") (pintype "output"))
    )
    (net (code "51") (name "Net-(U4A-BOOT0)") (class "Default")
      (node (ref "R6") (pin "2") (pinfunction "2_2") (pintype "passive"))
      (node (ref "U4") (pin "44") (pinfunction "BOOT0_44") (pintype "input"))
    )
    (net (code "52") (name "Net-(U4A-PA0-WKUP)") (class "Default")
      (node (ref "R11") (pin "1") (pinfunction "1_1") (pintype "passive"))
      (node (ref "R12") (pin "2") (pinfunction "2_2") (pintype "passive"))
      (node (ref "U4") (pin "10") (pinfunction "PA0-WKUP_10") (pintype "bidirectional"))
    )
    (net (code "53") (name "Net-(U4A-PB2)") (class "Default")
      (node (ref "R5") (pin "1") (pinfunction "1_1") (pintype "passive"))
      (node (ref "U4") (pin "20") (pinfunction "PB2_20") (pintype "bidirectional"))
    )
    (net (code "54") (name "Net-(U4A-PB3)") (class "Default")
      (node (ref "D4") (pin "A") (pinfunction "A_A") (pintype "passive"))
      (node (ref "U4") (pin "39") (pinfunction "PB3_39") (pintype "bidirectional"))
    )
    (net (code "55") (name "Net-(U4A-PB4)") (class "Default")
      (node (ref "D5") (pin "A") (pinfunction "A_A") (pintype "passive"))
      (node (ref "U4") (pin "40") (pinfunction "PB4_40") (pintype "bidirectional"))
    )
    (net (code "56") (name "Net-(U4A-PB5)") (class "Default")
      (node (ref "D6") (pin "A") (pinfunction "A_A") (pintype "passive"))
      (node (ref "U4") (pin "41") (pinfunction "PB5_41") (pintype "bidirectional"))
    )
    (net (code "57") (name "Net-(U4A-VBAT)") (class "Default")
      (node (ref "D2") (pin "C") (pinfunction "C_C") (pintype "passive"))
      (node (ref "U4") (pin "1") (pinfunction "VBAT_1") (pintype "power_in"))
    )
    (net (code "58") (name "Net-(U4A-VDDA)") (class "Default")
      (node (ref "C10") (pin "1") (pinfunction "1_1") (pintype "passive"))
      (node (ref "C8") (pin "1") (pinfunction "1_1") (pintype "passive"))
      (node (ref "C9") (pin "1") (pinfunction "1_1") (pintype "passive"))
      (node (ref "L1") (pin "1") (pinfunction "1_1") (pintype "passive"))
      (node (ref "U4") (pin "9") (pinfunction "VDDA_9") (pintype "power_in"))
    )
    (net (code "59") (name "Net-(U6A-I)") (class "Default")
      (node (ref "44E_A") (pin "3") (pinfunction "3_3") (pintype "passive"))
      (node (ref "C17") (pin "1") (pinfunction "1_1") (pintype "passive"))
      (node (ref "R7") (pin "1") (pinfunction "1_1") (pintype "passive"))
      (node (ref "U6") (pin "13") (pinfunction "I_13") (pintype "input"))
    )
    (net (code "60") (name "unconnected-(R9-Pad1)") (class "Default")
      (node (ref "R9") (pin "1") (pinfunction "1_1") (pintype "passive"))
    )
    (net (code "61") (name "unconnected-(R9A-2-Pad8)") (class "Default")
      (node (ref "R9") (pin "8") (pinfunction "2_8") (pintype "passive"))
    )
    (net (code "62") (name "unconnected-(U3-CTS-Pad23)") (class "Default")
      (node (ref "U3") (pin "23") (pinfunction "CTS_23") (pintype "input"))
    )
    (net (code "63") (name "unconnected-(U3-DCD-Pad1)") (class "Default")
      (node (ref "U3") (pin "1") (pinfunction "DCD_1") (pintype "input"))
    )
    (net (code "64") (name "unconnected-(U3-DSR-Pad27)") (class "Default")
      (node (ref "U3") (pin "27") (pinfunction "DSR_27") (pintype "input"))
    )
    (net (code "65") (name "unconnected-(U3-DTR-Pad28)") (class "Default")
      (node (ref "U3") (pin "28") (pinfunction "DTR_28") (pintype "output"))
    )
    (net (code "66") (name "unconnected-(U3-RI-Pad2)") (class "Default")
      (node (ref "U3") (pin "2") (pinfunction "RI_2") (pintype "input"))
    )
    (net (code "67") (name "unconnected-(U3-RTS-Pad24)") (class "Default")
      (node (ref "U3") (pin "24") (pinfunction "RTS_24") (pintype "output"))
    )
    (net (code "68") (name "unconnected-(U3-SUSPEND-Pad12)") (class "Default")
      (node (ref "U3") (pin "12") (pinfunction "SUSPEND_12") (pintype "output"))
    )
    (net (code "69") (name "unconnected-(U4A-OSC_OUT-Pad6)") (class "Default")
      (node (ref "U4") (pin "6") (pinfunction "OSC_OUT_6") (pintype "bidirectional"))
    )
    (net (code "70") (name "unconnected-(U4A-PA15-Pad38)") (class "Default")
      (node (ref "U4") (pin "38") (pinfunction "PA15_38") (pintype "bidirectional"))
    )
    (net (code "71") (name "unconnected-(U4A-PC13-Pad2)") (class "Default")
      (node (ref "U4") (pin "2") (pinfunction "PC13_2") (pintype "bidirectional"))
    )
    (net (code "72") (name "unconnected-(U4A-PC14-Pad3)") (class "Default")
      (node (ref "U4") (pin "3") (pinfunction "PC14_3") (pintype "bidirectional"))
    )
    (net (code "73") (name "unconnected-(U4A-PC15-Pad4)") (class "Default")
      (node (ref "U4") (pin "4") (pinfunction "PC15_4") (pintype "bidirectional"))
    )
    (net (code "74") (name "unconnected-(U5-1A-Pad3)") (class "Default")
      (node (ref "U5") (pin "3") (pinfunction "1A_3") (pintype "bidirectional"))
    )
    (net (code "75") (name "unconnected-(U5-1Y-Pad2)") (class "Default")
      (node (ref "U5") (pin "2") (pinfunction "1Y_2") (pintype "bidirectional"))
    )
    (net (code "76") (name "unconnected-(U5-2A-Pad5)") (class "Default")
      (node (ref "U5") (pin "5") (pinfunction "2A_5") (pintype "bidirectional"))
    )
    (net (code "77") (name "unconnected-(U5-2Y-Pad4)") (class "Default")
      (node (ref "U5") (pin "4") (pinfunction "2Y_4") (pintype "bidirectional"))
    )
    (net (code "78") (name "unconnected-(U5-3A-Pad7)") (class "Default")
      (node (ref "U5") (pin "7") (pinfunction "3A_7") (pintype "bidirectional"))
    )
    (net (code "79") (name "unconnected-(U5-3Y-Pad6)") (class "Default")
      (node (ref "U5") (pin "6") (pinfunction "3Y_6") (pintype "bidirectional"))
    )
    (net (code "80") (name "unconnected-(U5-4A-Pad9)") (class "Default")
      (node (ref "U5") (pin "9") (pinfunction "4A_9") (pintype "bidirectional"))
    )
    (net (code "81") (name "unconnected-(U5-4Y-Pad10)") (class "Default")
      (node (ref "U5") (pin "10") (pinfunction "4Y_10") (pintype "bidirectional"))
    )
    (net (code "82") (name "unconnected-(U6C-I-Pad9)") (class "Default")
      (node (ref "U6") (pin "9") (pinfunction "I_9") (pintype "input"))
    )
    (net (code "83") (name "unconnected-(U6C-O-Pad8)") (class "Default")
      (node (ref "U6") (pin "8") (pinfunction "O_8") (pintype "output"))
    )
    (net (code "84") (name "unconnected-(U6D-I-Pad1)") (class "Default")
      (node (ref "U6") (pin "1") (pinfunction "I_1") (pintype "input"))
    )
    (net (code "85") (name "unconnected-(U6D-O-Pad2)") (class "Default")
      (node (ref "U6") (pin "2") (pinfunction "O_2") (pintype "output"))
    )
    (net (code "86") (name "unconnected-(U6E-I-Pad3)") (class "Default")
      (node (ref "U6") (pin "3") (pinfunction "I_3") (pintype "input"))
    )
    (net (code "87") (name "unconnected-(U6E-O-Pad4)") (class "Default")
      (node (ref "U6") (pin "4") (pinfunction "O_4") (pintype "output"))
    )
    (net (code "88") (name "unconnected-(U6F-I-Pad5)") (class "Default")
      (node (ref "U6") (pin "5") (pinfunction "I_5") (pintype "input"))
    )
    (net (code "89") (name "unconnected-(U6F-O-Pad6)") (class "Default")
      (node (ref "U6") (pin "6") (pinfunction "O_6") (pintype "output"))
    )
  )
)
